# MFX.net
KiCad netlist of a schematic drawn in Altium Designer
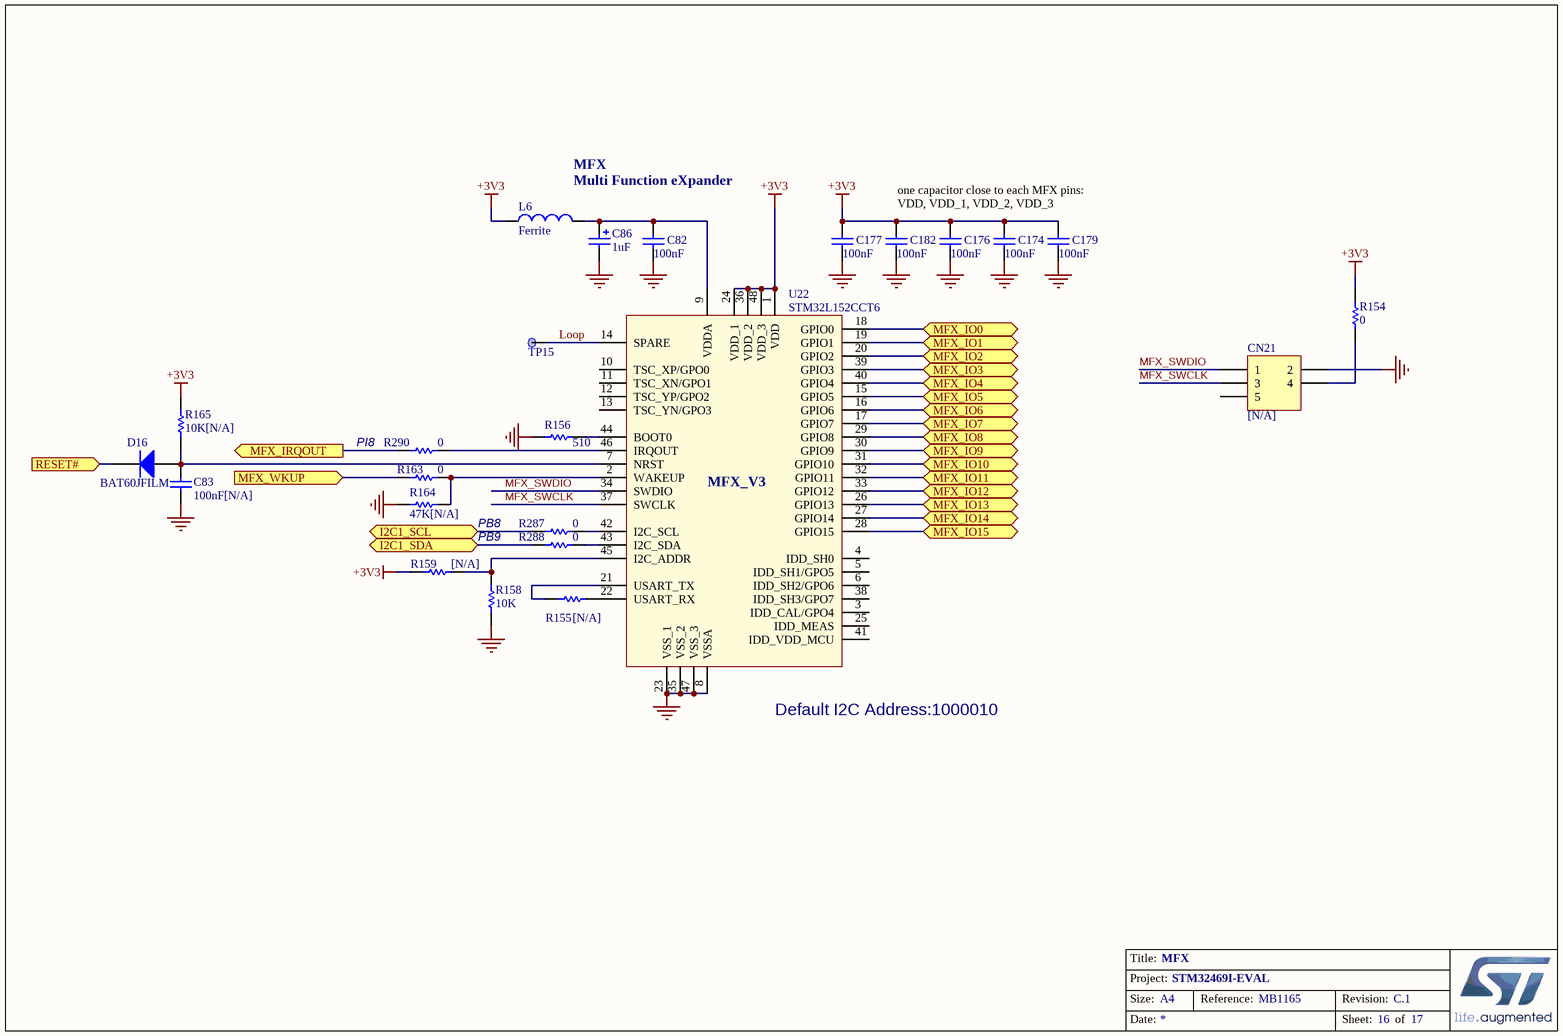
[diagram p0: MFX.SchDoc]

(export (version "E")
  (design (tool "Eeschema 10.0.6"))
  (components
    (comp (ref "C82")
      (value "100nF")
      (footprint "0402C")
      (description "Capacitor,100nF,16V,X7R,10%,0402,YAGEO")
      (libsource (lib "MCD_TOOLS") (part "Cap_100nF_X7R_10%_0402"))
    )
    (comp (ref "C83")
      (value "100nF[N/A]")
      (footprint "0402C")
      (description "Capacitor,100nF,16V,X7R,10%,0402,YAGEO")
      (libsource (lib "MCD_TOOLS") (part "Cap_100nF_X7R_10%_0402"))
    )
    (comp (ref "C86")
      (value "1uF")
      (footprint "TAN-A")
      (description "Polarized Capacitor,1uF,16V,10%,typeA,AVX")
      (libsource (lib "MCD_TOOLS") (part "Cap_1uF_POL_10%_TANA"))
    )
    (comp (ref "C174")
      (value "100nF")
      (footprint "0402C")
      (description "Capacitor,100nF,16V,X7R,10%,0402,YAGEO")
      (libsource (lib "MCD_TOOLS") (part "Cap_100nF_X7R_10%_0402"))
    )
    (comp (ref "C176")
      (value "100nF")
      (footprint "0402C")
      (description "Capacitor,100nF,16V,X7R,10%,0402,YAGEO")
      (libsource (lib "MCD_TOOLS") (part "Cap_100nF_X7R_10%_0402"))
    )
    (comp (ref "C177")
      (value "100nF")
      (footprint "0402C")
      (description "Capacitor,100nF,16V,X7R,10%,0402,YAGEO")
      (libsource (lib "MCD_TOOLS") (part "Cap_100nF_X7R_10%_0402"))
    )
    (comp (ref "C179")
      (value "100nF")
      (footprint "0402C")
      (description "Capacitor,100nF,16V,X7R,10%,0402,YAGEO")
      (libsource (lib "MCD_TOOLS") (part "Cap_100nF_X7R_10%_0402"))
    )
    (comp (ref "C182")
      (value "100nF")
      (footprint "0402C")
      (description "Capacitor,100nF,16V,X7R,10%,0402,YAGEO")
      (libsource (lib "MCD_TOOLS") (part "Cap_100nF_X7R_10%_0402"))
    )
    (comp (ref "CN21")
      (value "[N/A]")
      (footprint "HDR_2X3-1_2R54-6")
      (description "Header, 3-Pin, Dual row")
      (fields (field (name "PUBLISHER") "Altium Limited"))
      (libsource (lib "Miscellaneous Connectors") (part "Header 3X2"))
    )
    (comp (ref "D16")
      (value "BAT60JFILM")
      (footprint "SOD-323")
      (description "Default Diode")
      (fields (field (name "PUBLISHER") "Altium Limited"))
      (libsource (lib "Miscellaneous Devices") (part "Diode"))
    )
    (comp (ref "L6")
      (value "Ferrite")
      (footprint "0603L")
      (description "Bead,600R,350mA,0603,FCM1608KF-601T03,Tai-tech")
      (libsource (lib "MCD_TOOLS") (part "BEAD_600R_350MA_0603"))
    )
    (comp (ref "R154")
      (value "0")
      (footprint "0603R")
      (description "Resistor")
      (fields (field (name "PUBLISHER") "Altium Limited"))
      (libsource (lib "Miscellaneous Devices") (part "Res1"))
    )
    (comp (ref "R155")
      (value "[N/A]")
      (footprint "0603R")
      (description "Resistor")
      (fields (field (name "PUBLISHER") "Altium Limited"))
      (libsource (lib "Miscellaneous Devices") (part "res1"))
    )
    (comp (ref "R156")
      (value "510")
      (footprint "0402R")
      (description "Resistor 0402 or 0603 or 0805")
      (libsource (lib "MCD_TOOLS") (part "Resistor_ST"))
    )
    (comp (ref "R158")
      (value "10K")
      (footprint "0402R")
      (description "Resistor 0402 or 0603 or 0805")
      (libsource (lib "MCD_TOOLS") (part "Resistor_ST"))
    )
    (comp (ref "R159")
      (value "[N/A]")
      (footprint "0603R")
      (description "Resistor")
      (fields (field (name "PUBLISHER") "Altium Limited"))
      (libsource (lib "Miscellaneous Devices") (part "Res1"))
    )
    (comp (ref "R163")
      (value "0")
      (footprint "0603R")
      (description "Resistor")
      (fields (field (name "PUBLISHER") "Altium Limited"))
      (libsource (lib "Miscellaneous Devices") (part "Res1"))
    )
    (comp (ref "R164")
      (value "47K[N/A]")
      (footprint "0402R")
      (description "Resistor 0402 or 0603 or 0805")
      (libsource (lib "MCD_TOOLS") (part "Resistor_ST"))
    )
    (comp (ref "R165")
      (value "10K[N/A]")
      (footprint "0402R")
      (description "Resistor 0402 or 0603 or 0805")
      (libsource (lib "MCD_TOOLS") (part "Resistor_ST"))
    )
    (comp (ref "R287")
      (value "0")
      (footprint "0603R")
      (description "Resistor")
      (fields (field (name "PUBLISHER") "Altium Limited"))
      (libsource (lib "Miscellaneous Devices") (part "Res1"))
    )
    (comp (ref "R288")
      (value "0")
      (footprint "0603R")
      (description "Resistor")
      (fields (field (name "PUBLISHER") "Altium Limited"))
      (libsource (lib "Miscellaneous Devices") (part "Res1"))
    )
    (comp (ref "R290")
      (value "0")
      (footprint "0603R")
      (description "Resistor")
      (fields (field (name "PUBLISHER") "Altium Limited"))
      (libsource (lib "Miscellaneous Devices") (part "Res1"))
    )
    (comp (ref "TP15") (value "~") (footprint "TP") (libsource (lib "*") (part "TP")))
    (comp (ref "U22")
      (value "STM32L152CCT6")
      (footprint "LQFP48_0R5_9X9")
      (description "Multifunction expander")
      (libsource (lib "MB1167") (part "MFX"))
    )
  )
  (nets
    (net (code "1") (name "+3V3") (class "Default")
      (node (ref "C174") (pin "2") (pinfunction "2_2") (pintype "passive"))
      (node (ref "C176") (pin "1") (pinfunction "1_1") (pintype "passive"))
      (node (ref "C177") (pin "2") (pinfunction "2_2") (pintype "passive"))
      (node (ref "C179") (pin "2") (pinfunction "2_2") (pintype "passive"))
      (node (ref "C182") (pin "2") (pinfunction "2_2") (pintype "passive"))
      (node (ref "L6") (pin "1") (pinfunction "1_1") (pintype "passive"))
      (node (ref "R154") (pin "1") (pinfunction "1_1") (pintype "passive"))
      (node (ref "R159") (pin "2") (pinfunction "2_2") (pintype "passive"))
      (node (ref "R165") (pin "2") (pinfunction "2_2") (pintype "passive"))
      (node (ref "U22") (pin "1") (pinfunction "VDD_1") (pintype "passive"))
      (node (ref "U22") (pin "24") (pinfunction "VDD_1_24") (pintype "passive"))
      (node (ref "U22") (pin "36") (pinfunction "VDD_2_36") (pintype "passive"))
      (node (ref "U22") (pin "48") (pinfunction "VDD_3_48") (pintype "passive"))
    )
    (net (code "2") (name "/I2C1_SCL") (class "Default")
      (node (ref "R287") (pin "1") (pinfunction "1_1") (pintype "passive"))
    )
    (net (code "3") (name "/I2C1_SDA") (class "Default")
      (node (ref "R288") (pin "1") (pinfunction "1_1") (pintype "passive"))
    )
    (net (code "4") (name "/Loop") (class "Default")
      (node (ref "TP15") (pin "1") (pinfunction "1_1") (pintype "passive"))
      (node (ref "U22") (pin "14") (pinfunction "SPARE_14") (pintype "passive"))
    )
    (net (code "5") (name "/MFX_IO0") (class "Default")
      (node (ref "U22") (pin "18") (pinfunction "GPIO0_18") (pintype "passive"))
    )
    (net (code "6") (name "/MFX_IO1") (class "Default")
      (node (ref "U22") (pin "19") (pinfunction "GPIO1_19") (pintype "passive"))
    )
    (net (code "7") (name "/MFX_IO2") (class "Default")
      (node (ref "U22") (pin "20") (pinfunction "GPIO2_20") (pintype "passive"))
    )
    (net (code "8") (name "/MFX_IO3") (class "Default")
      (node (ref "U22") (pin "39") (pinfunction "GPIO3_39") (pintype "passive"))
    )
    (net (code "9") (name "/MFX_IO4") (class "Default")
      (node (ref "U22") (pin "40") (pinfunction "GPIO4_40") (pintype "passive"))
    )
    (net (code "10") (name "/MFX_IO5") (class "Default")
      (node (ref "U22") (pin "15") (pinfunction "GPIO5_15") (pintype "passive"))
    )
    (net (code "11") (name "/MFX_IO6") (class "Default")
      (node (ref "U22") (pin "16") (pinfunction "GPIO6_16") (pintype "passive"))
    )
    (net (code "12") (name "/MFX_IO7") (class "Default")
      (node (ref "U22") (pin "17") (pinfunction "GPIO7_17") (pintype "passive"))
    )
    (net (code "13") (name "/MFX_IO8") (class "Default")
      (node (ref "U22") (pin "29") (pinfunction "GPIO8_29") (pintype "passive"))
    )
    (net (code "14") (name "/MFX_IO9") (class "Default")
      (node (ref "U22") (pin "30") (pinfunction "GPIO9_30") (pintype "passive"))
    )
    (net (code "15") (name "/MFX_IO10") (class "Default")
      (node (ref "U22") (pin "31") (pinfunction "GPIO10_31") (pintype "passive"))
    )
    (net (code "16") (name "/MFX_IO11") (class "Default")
      (node (ref "U22") (pin "32") (pinfunction "GPIO11_32") (pintype "passive"))
    )
    (net (code "17") (name "/MFX_IO12") (class "Default")
      (node (ref "U22") (pin "33") (pinfunction "GPIO12_33") (pintype "passive"))
    )
    (net (code "18") (name "/MFX_IO13") (class "Default")
      (node (ref "U22") (pin "26") (pinfunction "GPIO13_26") (pintype "passive"))
    )
    (net (code "19") (name "/MFX_IO14") (class "Default")
      (node (ref "U22") (pin "27") (pinfunction "GPIO14_27") (pintype "passive"))
    )
    (net (code "20") (name "/MFX_IO15") (class "Default")
      (node (ref "U22") (pin "28") (pinfunction "GPIO15_28") (pintype "passive"))
    )
    (net (code "21") (name "/MFX_IRQOUT") (class "Default")
      (node (ref "R290") (pin "1") (pinfunction "1_1") (pintype "passive"))
    )
    (net (code "22") (name "/MFX_SWCLK") (class "Default")
      (node (ref "CN21") (pin "3") (pinfunction "3_3") (pintype "passive"))
      (node (ref "U22") (pin "37") (pinfunction "SWCLK_37") (pintype "passive"))
    )
    (net (code "23") (name "/MFX_SWDIO") (class "Default")
      (node (ref "CN21") (pin "1") (pinfunction "1_1") (pintype "passive"))
      (node (ref "U22") (pin "34") (pinfunction "SWDIO_34") (pintype "passive"))
    )
    (net (code "24") (name "/MFX_WKUP") (class "Default")
      (node (ref "R163") (pin "2") (pinfunction "2_2") (pintype "passive"))
    )
    (net (code "25") (name "/RESET#") (class "Default")
      (node (ref "D16") (pin "2") (pinfunction "K_2") (pintype "passive"))
    )
    (net (code "26") (name "GND") (class "Default")
      (node (ref "C174") (pin "1") (pinfunction "1_1") (pintype "passive"))
      (node (ref "C176") (pin "2") (pinfunction "2_2") (pintype "passive"))
      (node (ref "C177") (pin "1") (pinfunction "1_1") (pintype "passive"))
      (node (ref "C179") (pin "1") (pinfunction "1_1") (pintype "passive"))
      (node (ref "C182") (pin "1") (pinfunction "1_1") (pintype "passive"))
      (node (ref "C82") (pin "1") (pinfunction "1_1") (pintype "passive"))
      (node (ref "C83") (pin "1") (pinfunction "1_1") (pintype "passive"))
      (node (ref "C86") (pin "2") (pinfunction "2_2") (pintype "passive"))
      (node (ref "CN21") (pin "2") (pinfunction "2_2") (pintype "passive"))
      (node (ref "R156") (pin "2") (pinfunction "2_2") (pintype "passive"))
      (node (ref "R158") (pin "2") (pinfunction "2_2") (pintype "passive"))
      (node (ref "R164") (pin "1") (pinfunction "1_1") (pintype "passive"))
      (node (ref "U22") (pin "23") (pinfunction "VSS_1_23") (pintype "passive"))
      (node (ref "U22") (pin "35") (pinfunction "VSS_2_35") (pintype "passive"))
      (node (ref "U22") (pin "47") (pinfunction "VSS_3_47") (pintype "passive"))
      (node (ref "U22") (pin "8") (pinfunction "VSSA_8") (pintype "passive"))
    )
    (net (code "27") (name "Net-(CN21-Pad4)") (class "Default")
      (node (ref "CN21") (pin "4") (pinfunction "4_4") (pintype "passive"))
      (node (ref "R154") (pin "2") (pinfunction "2_2") (pintype "passive"))
    )
    (net (code "28") (name "Net-(D16-A)") (class "Default")
      (node (ref "C83") (pin "2") (pinfunction "2_2") (pintype "passive"))
      (node (ref "D16") (pin "1") (pinfunction "A_1") (pintype "passive"))
      (node (ref "R165") (pin "1") (pinfunction "1_1") (pintype "passive"))
      (node (ref "U22") (pin "7") (pinfunction "NRST_7") (pintype "passive"))
    )
    (net (code "29") (name "Net-(U22-BOOT0)") (class "Default")
      (node (ref "R156") (pin "1") (pinfunction "1_1") (pintype "passive"))
      (node (ref "U22") (pin "44") (pinfunction "BOOT0_44") (pintype "passive"))
    )
    (net (code "30") (name "Net-(U22-I2C_ADDR)") (class "Default")
      (node (ref "R158") (pin "1") (pinfunction "1_1") (pintype "passive"))
      (node (ref "R159") (pin "1") (pinfunction "1_1") (pintype "passive"))
      (node (ref "U22") (pin "45") (pinfunction "I2C_ADDR_45") (pintype "passive"))
    )
    (net (code "31") (name "Net-(U22-I2C_SCL)") (class "Default")
      (node (ref "R287") (pin "2") (pinfunction "2_2") (pintype "passive"))
      (node (ref "U22") (pin "42") (pinfunction "I2C_SCL_42") (pintype "passive"))
    )
    (net (code "32") (name "Net-(U22-I2C_SDA)") (class "Default")
      (node (ref "R288") (pin "2") (pinfunction "2_2") (pintype "passive"))
      (node (ref "U22") (pin "43") (pinfunction "I2C_SDA_43") (pintype "passive"))
    )
    (net (code "33") (name "Net-(U22-IRQOUT)") (class "Default")
      (node (ref "R290") (pin "2") (pinfunction "2_2") (pintype "passive"))
      (node (ref "U22") (pin "46") (pinfunction "IRQOUT_46") (pintype "passive"))
    )
    (net (code "34") (name "Net-(U22-USART_RX)") (class "Default")
      (node (ref "R155") (pin "2") (pinfunction "2_2") (pintype "passive"))
      (node (ref "U22") (pin "22") (pinfunction "USART_RX_22") (pintype "passive"))
    )
    (net (code "35") (name "Net-(U22-USART_TX)") (class "Default")
      (node (ref "R155") (pin "1") (pinfunction "1_1") (pintype "passive"))
      (node (ref "U22") (pin "21") (pinfunction "USART_TX_21") (pintype "passive"))
    )
    (net (code "36") (name "Net-(U22-VDDA)") (class "Default")
      (node (ref "C82") (pin "2") (pinfunction "2_2") (pintype "passive"))
      (node (ref "C86") (pin "1") (pinfunction "1_1") (pintype "passive"))
      (node (ref "L6") (pin "2") (pinfunction "2_2") (pintype "passive"))
      (node (ref "U22") (pin "9") (pinfunction "VDDA_9") (pintype "passive"))
    )
    (net (code "37") (name "Net-(U22-WAKEUP)") (class "Default")
      (node (ref "R163") (pin "1") (pinfunction "1_1") (pintype "passive"))
      (node (ref "R164") (pin "2") (pinfunction "2_2") (pintype "passive"))
      (node (ref "U22") (pin "2") (pinfunction "WAKEUP_2") (pintype "passive"))
    )
    (net (code "38") (name "unconnected-(CN21-Pad5)") (class "Default")
      (node (ref "CN21") (pin "5") (pinfunction "5_5") (pintype "passive"))
    )
    (net (code "39") (name "unconnected-(U22-IDD_CAL{slash}GPO4-Pad3)") (class "Default")
      (node (ref "U22") (pin "3") (pinfunction "IDD_CAL/GPO4_3") (pintype "passive"))
    )
    (net (code "40") (name "unconnected-(U22-IDD_MEAS-Pad25)") (class "Default")
      (node (ref "U22") (pin "25") (pinfunction "IDD_MEAS_25") (pintype "passive"))
    )
    (net (code "41") (name "unconnected-(U22-IDD_SH0-Pad4)") (class "Default")
      (node (ref "U22") (pin "4") (pinfunction "IDD_SH0_4") (pintype "passive"))
    )
    (net (code "42") (name "unconnected-(U22-IDD_SH1{slash}GPO5-Pad5)") (class "Default")
      (node (ref "U22") (pin "5") (pinfunction "IDD_SH1/GPO5_5") (pintype "passive"))
    )
    (net (code "43") (name "unconnected-(U22-IDD_SH2{slash}GPO6-Pad6)") (class "Default")
      (node (ref "U22") (pin "6") (pinfunction "IDD_SH2/GPO6_6") (pintype "passive"))
    )
    (net (code "44") (name "unconnected-(U22-IDD_SH3{slash}GPO7-Pad38)") (class "Default")
      (node (ref "U22") (pin "38") (pinfunction "IDD_SH3/GPO7_38") (pintype "passive"))
    )
    (net (code "45") (name "unconnected-(U22-IDD_VDD_MCU-Pad41)") (class "Default")
      (node (ref "U22") (pin "41") (pinfunction "IDD_VDD_MCU_41") (pintype "passive"))
    )
    (net (code "46") (name "unconnected-(U22-TSC_XN{slash}GPO1-Pad11)") (class "Default")
      (node (ref "U22") (pin "11") (pinfunction "TSC_XN/GPO1_11") (pintype "passive"))
    )
    (net (code "47") (name "unconnected-(U22-TSC_XP{slash}GPO0-Pad10)") (class "Default")
      (node (ref "U22") (pin "10") (pinfunction "TSC_XP/GPO0_10") (pintype "passive"))
    )
    (net (code "48") (name "unconnected-(U22-TSC_YN{slash}GPO3-Pad13)") (class "Default")
      (node (ref "U22") (pin "13") (pinfunction "TSC_YN/GPO3_13") (pintype "passive"))
    )
    (net (code "49") (name "unconnected-(U22-TSC_YP{slash}GPO2-Pad12)") (class "Default")
      (node (ref "U22") (pin "12") (pinfunction "TSC_YP/GPO2_12") (pintype "passive"))
    )
  )
)
